# Custom_IMU_testing.net
KiCad netlist of a schematic drawn in Altium Designer
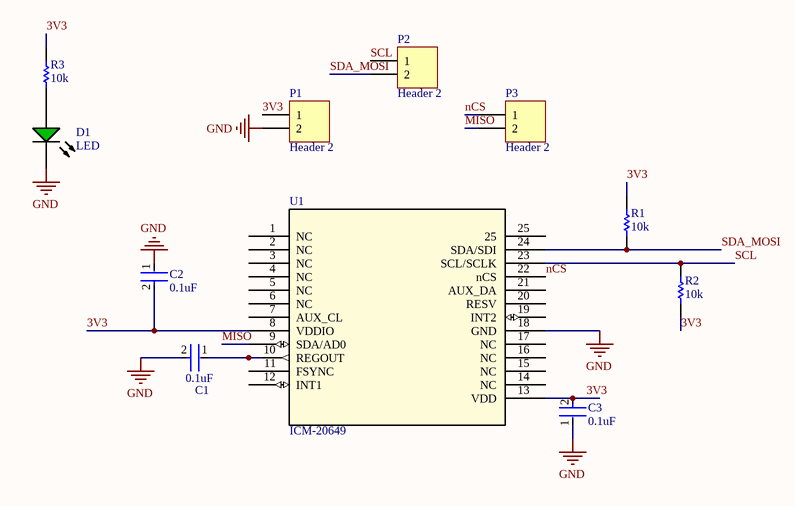
[diagram p0: Custom_IMU_testing.SchDoc]

(export (version "E")
  (design (tool "Eeschema 10.0.6"))
  (components
    (comp (ref "C1")
      (value "0.1uF")
      (footprint "FP-GRM15-MFG")
      (description "CAP CER 0.1UF 16V X7R 0402")
      (fields (field (name "MANUFACTURER PART NUMBER") "GRM155R71C104KA88D") (field (name "TOLERANCE") "10%"))
      (libsource (lib "Altium Content Vault") (part "236180d848d6139a670b325ea6854c9"))
    )
    (comp (ref "C2")
      (value "0.1uF")
      (footprint "FP-GRM15-MFG")
      (description "CAP CER 0.1UF 16V X7R 0402")
      (fields (field (name "MANUFACTURER PART NUMBER") "GRM155R71C104KA88D") (field (name "TOLERANCE") "10%"))
      (libsource (lib "Altium Content Vault") (part "236180d848d6139a670b325ea6854c9"))
    )
    (comp (ref "C3")
      (value "0.1uF")
      (footprint "FP-GRM15-MFG")
      (description "CAP CER 0.1UF 16V X7R 0402")
      (fields (field (name "MANUFACTURER PART NUMBER") "GRM155R71C104KA88D") (field (name "TOLERANCE") "10%"))
      (libsource (lib "Altium Content Vault") (part "236180d848d6139a670b325ea6854c9"))
    )
    (comp (ref "D1")
      (value "LED")
      (footprint "LED-2P-2.54-3MM_V")
      (description "LED, Green, 2 mA, 1.9 V, -20 to 100 degC, 2-Pin THD, RoHS, Bulk")
      (fields (field (name "MANUFACTURER") "Avago"))
      (libsource (lib "Altium Content Vault") (part "LED_GREEN_A1K2-2"))
    )
    (comp (ref "P1")
      (value "Header 2")
      (footprint "HDR1X2")
      (description "Header, 2-Pin")
      (fields (field (name "PUBLISHER") "Altium Limited"))
      (libsource (lib "Miscellaneous Connectors") (part "Header 2"))
    )
    (comp (ref "P2")
      (value "Header 2")
      (footprint "HDR1X2")
      (description "Header, 2-Pin")
      (fields (field (name "PUBLISHER") "Altium Limited"))
      (libsource (lib "Miscellaneous Connectors") (part "Header 2"))
    )
    (comp (ref "P3")
      (value "Header 2")
      (footprint "HDR1X2")
      (description "Header, 2-Pin")
      (fields (field (name "PUBLISHER") "Altium Limited"))
      (libsource (lib "Miscellaneous Connectors") (part "Header 2"))
    )
    (comp (ref "R1")
      (value "10k")
      (footprint "RESC1005X40X25LL05T10")
      (fields (field (name "PART NUMBER") "RC0402FR-0710KL") (field (name "MANUFACTURER") "Yageo / Phycomp"))
      (libsource (lib "Altium Content Vault") (part "RES"))
    )
    (comp (ref "R2")
      (value "10k")
      (footprint "RESC1005X40X25LL05T10")
      (fields (field (name "PART NUMBER") "RC0402FR-0710KL") (field (name "MANUFACTURER") "Yageo / Phycomp"))
      (libsource (lib "Altium Content Vault") (part "RES"))
    )
    (comp (ref "R3")
      (value "10k")
      (footprint "RESC1005X40X25LL05T10")
      (fields (field (name "PART NUMBER") "RC0402FR-0710KL") (field (name "MANUFACTURER") "Yageo / Phycomp"))
      (libsource (lib "Altium Content Vault") (part "RES"))
    )
    (comp (ref "U1")
      (value "ICM-20649")
      (footprint "QFN24_3X3X0P9_IVS")
      (description "No Description Available")
      (fields (field (name "COPYRIGHT") "Copyright (C) 2023 Ultra Librarian. All rights reserved."))
      (libsource (lib "ICM-20649") (part "ICM-20649"))
    )
  )
  (nets
    (net (code "1") (name "/3V3") (class "Default")
      (node (ref "C2") (pin "2") (pinfunction "2_2") (pintype "passive"))
      (node (ref "C3") (pin "2") (pinfunction "2_2") (pintype "passive"))
      (node (ref "P1") (pin "1") (pinfunction "1_1") (pintype "passive"))
      (node (ref "R1") (pin "2") (pinfunction "2_2") (pintype "passive"))
      (node (ref "R2") (pin "1") (pinfunction "1_1") (pintype "passive"))
      (node (ref "R3") (pin "2") (pinfunction "2_2") (pintype "passive"))
      (node (ref "U1") (pin "13") (pinfunction "VDD_13") (pintype "power_in"))
      (node (ref "U1") (pin "8") (pinfunction "VDDIO_8") (pintype "power_in"))
    )
    (net (code "2") (name "/MISO") (class "Default")
      (node (ref "P3") (pin "2") (pinfunction "2_2") (pintype "passive"))
      (node (ref "U1") (pin "9") (pinfunction "SDA/AD0_9") (pintype "bidirectional"))
    )
    (net (code "3") (name "/SCL") (class "Default")
      (node (ref "P2") (pin "1") (pinfunction "1_1") (pintype "passive"))
      (node (ref "R2") (pin "2") (pinfunction "2_2") (pintype "passive"))
      (node (ref "U1") (pin "23") (pinfunction "SCL/SCLK_23") (pintype "passive"))
    )
    (net (code "4") (name "/SDA_MOSI") (class "Default")
      (node (ref "P2") (pin "2") (pinfunction "2_2") (pintype "passive"))
      (node (ref "R1") (pin "1") (pinfunction "1_1") (pintype "passive"))
      (node (ref "U1") (pin "24") (pinfunction "SDA/SDI_24") (pintype "passive"))
    )
    (net (code "5") (name "/nCS") (class "Default")
      (node (ref "P3") (pin "1") (pinfunction "1_1") (pintype "passive"))
      (node (ref "U1") (pin "22") (pinfunction "nCS_22") (pintype "passive"))
    )
    (net (code "6") (name "GND") (class "Default")
      (node (ref "C1") (pin "2") (pinfunction "2_2") (pintype "passive"))
      (node (ref "C2") (pin "1") (pinfunction "1_1") (pintype "passive"))
      (node (ref "C3") (pin "1") (pinfunction "1_1") (pintype "passive"))
      (node (ref "D1") (pin "2") (pinfunction "K_2") (pintype "passive"))
      (node (ref "P1") (pin "2") (pinfunction "2_2") (pintype "passive"))
      (node (ref "U1") (pin "18") (pinfunction "GND_18") (pintype "passive"))
    )
    (net (code "7") (name "Net-(D1-A)") (class "Default")
      (node (ref "D1") (pin "1") (pinfunction "A_1") (pintype "passive"))
      (node (ref "R3") (pin "1") (pinfunction "1_1") (pintype "passive"))
    )
    (net (code "8") (name "Net-(U1-REGOUT)") (class "Default")
      (node (ref "C1") (pin "1") (pinfunction "1_1") (pintype "passive"))
      (node (ref "U1") (pin "10") (pinfunction "REGOUT_10") (pintype "output"))
    )
    (net (code "9") (name "unconnected-(U1-AUX_CL-Pad7)") (class "Default")
      (node (ref "U1") (pin "7") (pinfunction "AUX_CL_7") (pintype "passive"))
    )
    (net (code "10") (name "unconnected-(U1-AUX_DA-Pad21)") (class "Default")
      (node (ref "U1") (pin "21") (pinfunction "AUX_DA_21") (pintype "passive"))
    )
    (net (code "11") (name "unconnected-(U1-FSYNC-Pad11)") (class "Default")
      (node (ref "U1") (pin "11") (pinfunction "FSYNC_11") (pintype "passive"))
    )
    (net (code "12") (name "unconnected-(U1-INT1-Pad12)") (class "Default")
      (node (ref "U1") (pin "12") (pinfunction "INT1_12") (pintype "bidirectional"))
    )
    (net (code "13") (name "unconnected-(U1-INT2-Pad19)") (class "Default")
      (node (ref "U1") (pin "19") (pinfunction "INT2_19") (pintype "bidirectional"))
    )
    (net (code "14") (name "unconnected-(U1-NC-Pad1)") (class "Default")
      (node (ref "U1") (pin "1") (pinfunction "NC_1") (pintype "passive"))
    )
    (net (code "15") (name "unconnected-(U1-NC-Pad2)") (class "Default")
      (node (ref "U1") (pin "2") (pinfunction "NC_2") (pintype "passive"))
    )
    (net (code "16") (name "unconnected-(U1-NC-Pad3)") (class "Default")
      (node (ref "U1") (pin "3") (pinfunction "NC_3") (pintype "passive"))
    )
    (net (code "17") (name "unconnected-(U1-NC-Pad4)") (class "Default")
      (node (ref "U1") (pin "4") (pinfunction "NC_4") (pintype "passive"))
    )
    (net (code "18") (name "unconnected-(U1-NC-Pad5)") (class "Default")
      (node (ref "U1") (pin "5") (pinfunction "NC_5") (pintype "passive"))
    )
    (net (code "19") (name "unconnected-(U1-NC-Pad6)") (class "Default")
      (node (ref "U1") (pin "6") (pinfunction "NC_6") (pintype "passive"))
    )
    (net (code "20") (name "unconnected-(U1-NC-Pad14)") (class "Default")
      (node (ref "U1") (pin "14") (pinfunction "NC_14") (pintype "passive"))
    )
    (net (code "21") (name "unconnected-(U1-NC-Pad15)") (class "Default")
      (node (ref "U1") (pin "15") (pinfunction "NC_15") (pintype "passive"))
    )
    (net (code "22") (name "unconnected-(U1-NC-Pad16)") (class "Default")
      (node (ref "U1") (pin "16") (pinfunction "NC_16") (pintype "passive"))
    )
    (net (code "23") (name "unconnected-(U1-NC-Pad17)") (class "Default")
      (node (ref "U1") (pin "17") (pinfunction "NC_17") (pintype "passive"))
    )
    (net (code "24") (name "unconnected-(U1-Pad25)") (class "Default")
      (node (ref "U1") (pin "25") (pinfunction "25_25") (pintype "passive"))
    )
    (net (code "25") (name "unconnected-(U1-RESV-Pad20)") (class "Default")
      (node (ref "U1") (pin "20") (pinfunction "RESV_20") (pintype "passive"))
    )
  )
)
